# lora.net
KiCad netlist of a schematic drawn in Altium Designer
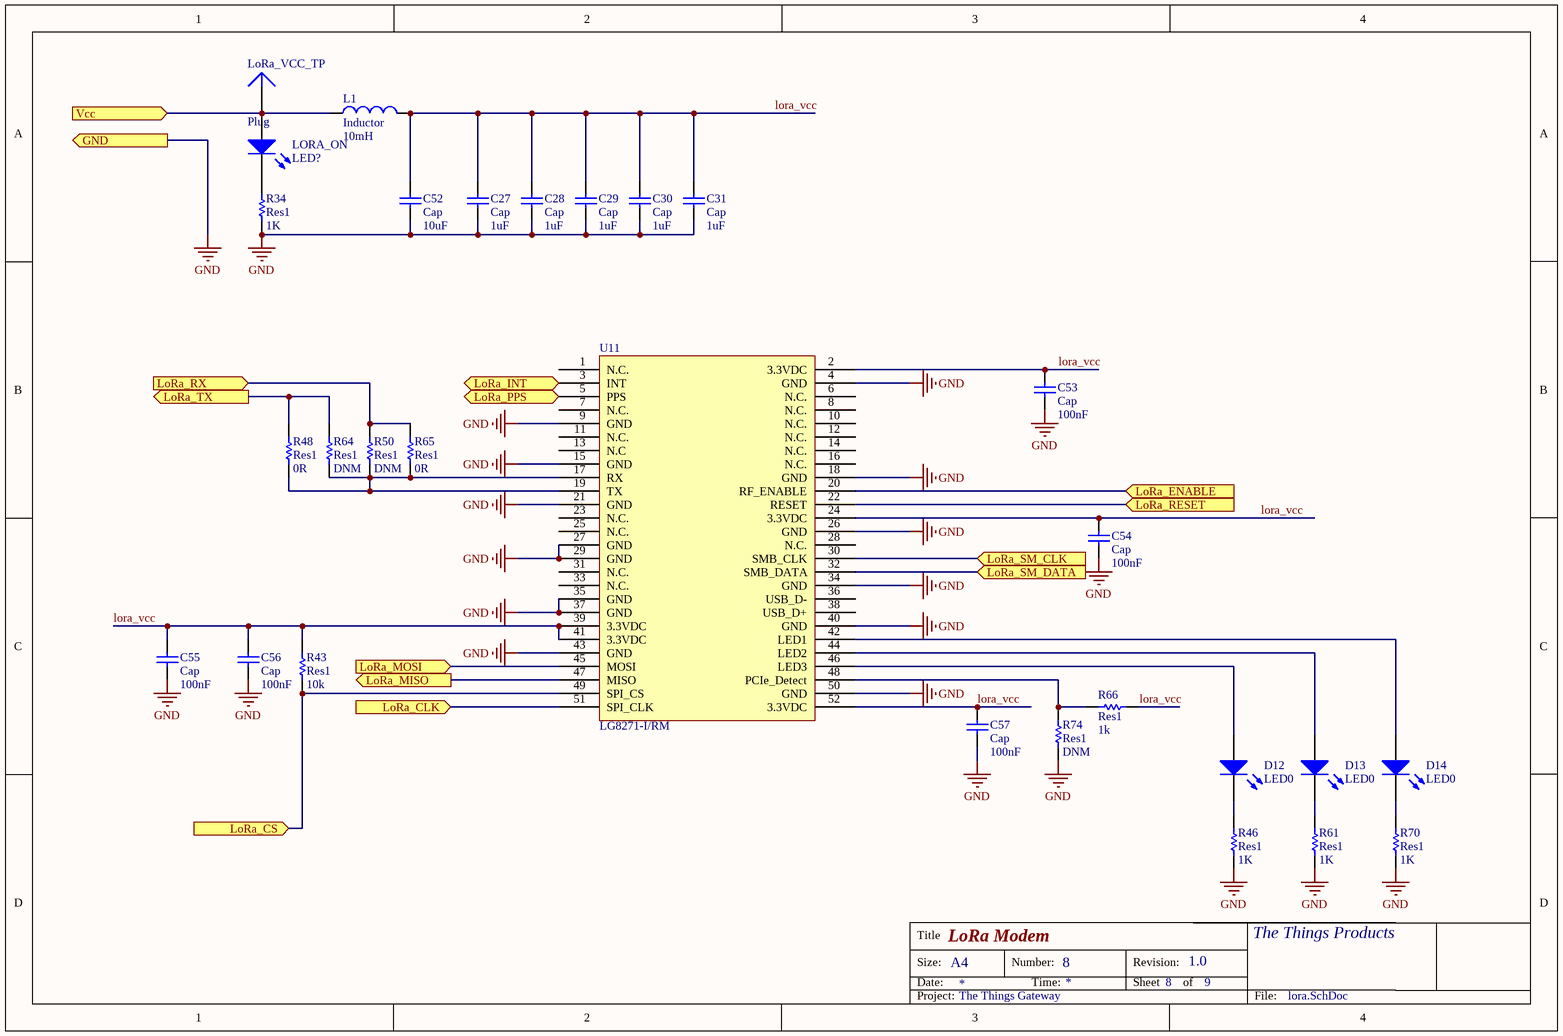
[diagram p0: lora.SchDoc]

(export (version "E")
  (design (tool "Eeschema 10.0.6"))
  (components
    (comp (ref "C27")
      (value "Cap")
      (footprint "C1206")
      (description "Capacitor")
      (fields (field (name "ALTIUM_VALUE") "1uF") (field (name "PUBLISHER") "Altium Limited"))
      (libsource (lib "any") (part "Cap"))
    )
    (comp (ref "C28")
      (value "Cap")
      (footprint "C1206")
      (description "Capacitor")
      (fields (field (name "ALTIUM_VALUE") "1uF") (field (name "PUBLISHER") "Altium Limited"))
      (libsource (lib "any") (part "Cap"))
    )
    (comp (ref "C29")
      (value "Cap")
      (footprint "C1206")
      (description "Capacitor")
      (fields (field (name "ALTIUM_VALUE") "1uF") (field (name "PUBLISHER") "Altium Limited"))
      (libsource (lib "any") (part "Cap"))
    )
    (comp (ref "C30")
      (value "Cap")
      (footprint "C1206")
      (description "Capacitor")
      (fields (field (name "ALTIUM_VALUE") "1uF") (field (name "PUBLISHER") "Altium Limited"))
      (libsource (lib "any") (part "Cap"))
    )
    (comp (ref "C31")
      (value "Cap")
      (footprint "C1206")
      (description "Capacitor")
      (fields (field (name "ALTIUM_VALUE") "1uF") (field (name "PUBLISHER") "Altium Limited"))
      (libsource (lib "any") (part "Cap"))
    )
    (comp (ref "C52")
      (value "Cap")
      (footprint "C1206")
      (description "Capacitor")
      (fields (field (name "ALTIUM_VALUE") "10uF") (field (name "PUBLISHER") "Altium Limited"))
      (libsource (lib "any") (part "Cap"))
    )
    (comp (ref "C53")
      (value "Cap")
      (footprint "C0603")
      (description "Capacitor")
      (fields (field (name "ALTIUM_VALUE") "100nF") (field (name "PUBLISHER") "Altium Limited"))
      (libsource (lib "any") (part "Cap"))
    )
    (comp (ref "C54")
      (value "Cap")
      (footprint "C0603")
      (description "Capacitor")
      (fields (field (name "ALTIUM_VALUE") "100nF") (field (name "PUBLISHER") "Altium Limited"))
      (libsource (lib "any") (part "Cap"))
    )
    (comp (ref "C55")
      (value "Cap")
      (footprint "C0603")
      (description "Capacitor")
      (fields (field (name "ALTIUM_VALUE") "100nF") (field (name "PUBLISHER") "Altium Limited"))
      (libsource (lib "any") (part "Cap"))
    )
    (comp (ref "C56")
      (value "Cap")
      (footprint "C0603")
      (description "Capacitor")
      (fields (field (name "ALTIUM_VALUE") "100nF") (field (name "PUBLISHER") "Altium Limited"))
      (libsource (lib "any") (part "Cap"))
    )
    (comp (ref "C57")
      (value "Cap")
      (footprint "C0603")
      (description "Capacitor")
      (fields (field (name "ALTIUM_VALUE") "100nF") (field (name "PUBLISHER") "Altium Limited"))
      (libsource (lib "any") (part "Cap"))
    )
    (comp (ref "D12")
      (value "LED0")
      (footprint "C0603")
      (description "Typical INFRARED GaAs LED")
      (fields (field (name "PUBLISHER") "Altium Limited"))
      (libsource (lib "any") (part "LED0"))
    )
    (comp (ref "D13")
      (value "LED0")
      (footprint "C0603")
      (description "Typical INFRARED GaAs LED")
      (fields (field (name "PUBLISHER") "Altium Limited"))
      (libsource (lib "any") (part "LED0"))
    )
    (comp (ref "D14")
      (value "LED0")
      (footprint "C0603")
      (description "Typical INFRARED GaAs LED")
      (fields (field (name "PUBLISHER") "Altium Limited"))
      (libsource (lib "any") (part "LED0"))
    )
    (comp (ref "L1")
      (value "Inductor")
      (footprint "2029")
      (fields (field (name "ALTIUM_VALUE") "10mH") (field (name "PUBLISHER") "Altium Limited"))
      (libsource (lib "Miscellaneous Devices") (part "Inductor"))
    )
    (comp (ref "LORA_ON")
      (value "LED?")
      (footprint "C0603")
      (description "Typical INFRARED GaAs LED")
      (fields (field (name "PUBLISHER") "Altium Limited"))
      (libsource (lib "any") (part "LED0"))
    )
    (comp (ref "LoRa_VCC_TP")
      (value "Plug")
      (footprint "PIN1")
      (fields (field (name "PUBLISHER") "Altium Limited"))
      (libsource (lib "Miscellaneous Connectors") (part "Plug"))
    )
    (comp (ref "R34")
      (value "Res1")
      (footprint "R0603")
      (description "Resistor")
      (fields (field (name "ALTIUM_VALUE") "1K") (field (name "PUBLISHER") "Altium Limited"))
      (libsource (lib "any") (part "Res1"))
    )
    (comp (ref "R43")
      (value "Res1")
      (footprint "R0603")
      (description "Resistor")
      (fields (field (name "ALTIUM_VALUE") "10k") (field (name "PUBLISHER") "Altium Limited"))
      (libsource (lib "any") (part "Res1"))
    )
    (comp (ref "R46")
      (value "Res1")
      (footprint "R0603")
      (description "Resistor")
      (fields (field (name "ALTIUM_VALUE") "1K") (field (name "PUBLISHER") "Altium Limited"))
      (libsource (lib "any") (part "Res1"))
    )
    (comp (ref "R48")
      (value "Res1")
      (footprint "R0603")
      (description "Resistor")
      (fields (field (name "ALTIUM_VALUE") "0R") (field (name "PUBLISHER") "Altium Limited"))
      (libsource (lib "any") (part "Res1"))
    )
    (comp (ref "R50")
      (value "Res1")
      (footprint "R0603")
      (description "Resistor")
      (fields (field (name "ALTIUM_VALUE") "DNM") (field (name "PUBLISHER") "Altium Limited"))
      (libsource (lib "any") (part "Res1"))
    )
    (comp (ref "R61")
      (value "Res1")
      (footprint "R0603")
      (description "Resistor")
      (fields (field (name "ALTIUM_VALUE") "1K") (field (name "PUBLISHER") "Altium Limited"))
      (libsource (lib "any") (part "Res1"))
    )
    (comp (ref "R64")
      (value "Res1")
      (footprint "R0603")
      (description "Resistor")
      (fields (field (name "ALTIUM_VALUE") "DNM") (field (name "PUBLISHER") "Altium Limited"))
      (libsource (lib "any") (part "Res1"))
    )
    (comp (ref "R65")
      (value "Res1")
      (footprint "R0603")
      (description "Resistor")
      (fields (field (name "ALTIUM_VALUE") "0R") (field (name "PUBLISHER") "Altium Limited"))
      (libsource (lib "any") (part "Res1"))
    )
    (comp (ref "R66")
      (value "Res1")
      (footprint "R0603")
      (description "Resistor")
      (fields (field (name "ALTIUM_VALUE") "1k") (field (name "PUBLISHER") "Altium Limited"))
      (libsource (lib "any") (part "Res1"))
    )
    (comp (ref "R70")
      (value "Res1")
      (footprint "R0603")
      (description "Resistor")
      (fields (field (name "ALTIUM_VALUE") "1K") (field (name "PUBLISHER") "Altium Limited"))
      (libsource (lib "any") (part "Res1"))
    )
    (comp (ref "R74")
      (value "Res1")
      (footprint "R0603")
      (description "Resistor")
      (fields (field (name "ALTIUM_VALUE") "DNM") (field (name "PUBLISHER") "Altium Limited"))
      (libsource (lib "any") (part "Res1"))
    )
    (comp (ref "U11")
      (value "LG8271-I/RM")
      (footprint "BTB-SM0-8-2H52F")
      (description "Microchip Mini PCI Express LoRa Radio")
      (libsource (lib "ttn_schematic_library") (part "MCP LoRa Gateway"))
    )
  )
  (nets
    (net (code "1") (name "/LoRa_CLK") (class "Default")
      (node (ref "U11") (pin "51") (pinfunction "SPI_CLK_51") (pintype "passive"))
    )
    (net (code "2") (name "/LoRa_CS") (class "Default")
      (node (ref "R43") (pin "1") (pinfunction "1_1") (pintype "passive"))
      (node (ref "U11") (pin "49") (pinfunction "SPI_CS_49") (pintype "passive"))
    )
    (net (code "3") (name "/LoRa_ENABLE") (class "Default")
      (node (ref "U11") (pin "20") (pinfunction "RF_ENABLE_20") (pintype "passive"))
    )
    (net (code "4") (name "/LoRa_INT") (class "Default")
      (node (ref "U11") (pin "3") (pinfunction "INT_3") (pintype "passive"))
    )
    (net (code "5") (name "/LoRa_MISO") (class "Default")
      (node (ref "U11") (pin "47") (pinfunction "MISO_47") (pintype "passive"))
    )
    (net (code "6") (name "/LoRa_MOSI") (class "Default")
      (node (ref "U11") (pin "45") (pinfunction "MOSI_45") (pintype "passive"))
    )
    (net (code "7") (name "/LoRa_PPS") (class "Default")
      (node (ref "U11") (pin "5") (pinfunction "PPS_5") (pintype "passive"))
    )
    (net (code "8") (name "/LoRa_RESET") (class "Default")
      (node (ref "U11") (pin "22") (pinfunction "RESET_22") (pintype "passive"))
    )
    (net (code "9") (name "/LoRa_RX") (class "Default")
      (node (ref "R50") (pin "2") (pinfunction "2_2") (pintype "passive"))
      (node (ref "R65") (pin "1") (pinfunction "1_1") (pintype "passive"))
    )
    (net (code "10") (name "/LoRa_SM_CLK") (class "Default")
      (node (ref "U11") (pin "30") (pinfunction "SMB_CLK_30") (pintype "passive"))
    )
    (net (code "11") (name "/LoRa_SM_DATA") (class "Default")
      (node (ref "U11") (pin "32") (pinfunction "SMB_DATA_32") (pintype "passive"))
    )
    (net (code "12") (name "/LoRa_TX") (class "Default")
      (node (ref "R48") (pin "2") (pinfunction "2_2") (pintype "passive"))
      (node (ref "R64") (pin "2") (pinfunction "2_2") (pintype "passive"))
    )
    (net (code "13") (name "/Vcc") (class "Default")
      (node (ref "L1") (pin "1") (pinfunction "1_1") (pintype "passive"))
      (node (ref "LORA_ON") (pin "1") (pinfunction "A_1") (pintype "passive"))
      (node (ref "LoRa_VCC_TP") (pin "1") (pinfunction "1_1") (pintype "passive"))
    )
    (net (code "14") (name "/lora_vcc") (class "Default")
      (node (ref "C27") (pin "2") (pinfunction "2_2") (pintype "passive"))
      (node (ref "C28") (pin "2") (pinfunction "2_2") (pintype "passive"))
      (node (ref "C29") (pin "2") (pinfunction "2_2") (pintype "passive"))
      (node (ref "C30") (pin "2") (pinfunction "2_2") (pintype "passive"))
      (node (ref "C31") (pin "2") (pinfunction "2_2") (pintype "passive"))
      (node (ref "C52") (pin "2") (pinfunction "2_2") (pintype "passive"))
      (node (ref "C53") (pin "2") (pinfunction "2_2") (pintype "passive"))
      (node (ref "C54") (pin "2") (pinfunction "2_2") (pintype "passive"))
      (node (ref "C55") (pin "2") (pinfunction "2_2") (pintype "passive"))
      (node (ref "C56") (pin "2") (pinfunction "2_2") (pintype "passive"))
      (node (ref "C57") (pin "2") (pinfunction "2_2") (pintype "passive"))
      (node (ref "L1") (pin "2") (pinfunction "2_2") (pintype "passive"))
      (node (ref "R43") (pin "2") (pinfunction "2_2") (pintype "passive"))
      (node (ref "R66") (pin "1") (pinfunction "1_1") (pintype "passive"))
      (node (ref "U11") (pin "2") (pinfunction "3.3VDC_2") (pintype "passive"))
      (node (ref "U11") (pin "24") (pinfunction "3.3VDC_24") (pintype "passive"))
      (node (ref "U11") (pin "39") (pinfunction "3.3VDC_39") (pintype "passive"))
      (node (ref "U11") (pin "41") (pinfunction "3.3VDC_41") (pintype "passive"))
      (node (ref "U11") (pin "52") (pinfunction "3.3VDC_52") (pintype "passive"))
    )
    (net (code "15") (name "GND") (class "Default")
      (node (ref "C27") (pin "1") (pinfunction "1_1") (pintype "passive"))
      (node (ref "C28") (pin "1") (pinfunction "1_1") (pintype "passive"))
      (node (ref "C29") (pin "1") (pinfunction "1_1") (pintype "passive"))
      (node (ref "C30") (pin "1") (pinfunction "1_1") (pintype "passive"))
      (node (ref "C31") (pin "1") (pinfunction "1_1") (pintype "passive"))
      (node (ref "C52") (pin "1") (pinfunction "1_1") (pintype "passive"))
      (node (ref "C53") (pin "1") (pinfunction "1_1") (pintype "passive"))
      (node (ref "C54") (pin "1") (pinfunction "1_1") (pintype "passive"))
      (node (ref "C55") (pin "1") (pinfunction "1_1") (pintype "passive"))
      (node (ref "C56") (pin "1") (pinfunction "1_1") (pintype "passive"))
      (node (ref "C57") (pin "1") (pinfunction "1_1") (pintype "passive"))
      (node (ref "R34") (pin "1") (pinfunction "1_1") (pintype "passive"))
      (node (ref "R46") (pin "1") (pinfunction "1_1") (pintype "passive"))
      (node (ref "R61") (pin "1") (pinfunction "1_1") (pintype "passive"))
      (node (ref "R70") (pin "1") (pinfunction "1_1") (pintype "passive"))
      (node (ref "R74") (pin "1") (pinfunction "1_1") (pintype "passive"))
      (node (ref "U11") (pin "15") (pinfunction "GND_15") (pintype "passive"))
      (node (ref "U11") (pin "18") (pinfunction "GND_18") (pintype "passive"))
      (node (ref "U11") (pin "21") (pinfunction "GND_21") (pintype "passive"))
      (node (ref "U11") (pin "26") (pinfunction "GND_26") (pintype "passive"))
      (node (ref "U11") (pin "27") (pinfunction "GND_27") (pintype "passive"))
      (node (ref "U11") (pin "29") (pinfunction "GND_29") (pintype "passive"))
      (node (ref "U11") (pin "34") (pinfunction "GND_34") (pintype "passive"))
      (node (ref "U11") (pin "35") (pinfunction "GND_35") (pintype "passive"))
      (node (ref "U11") (pin "37") (pinfunction "GND_37") (pintype "passive"))
      (node (ref "U11") (pin "4") (pinfunction "GND_4") (pintype "passive"))
      (node (ref "U11") (pin "40") (pinfunction "GND_40") (pintype "passive"))
      (node (ref "U11") (pin "43") (pinfunction "GND_43") (pintype "passive"))
      (node (ref "U11") (pin "50") (pinfunction "GND_50") (pintype "passive"))
      (node (ref "U11") (pin "9") (pinfunction "GND_9") (pintype "passive"))
    )
    (net (code "16") (name "Net-(D12-A)") (class "Default")
      (node (ref "D12") (pin "1") (pinfunction "A_1") (pintype "passive"))
      (node (ref "U11") (pin "46") (pinfunction "LED3_46") (pintype "passive"))
    )
    (net (code "17") (name "Net-(D12-K)") (class "Default")
      (node (ref "D12") (pin "2") (pinfunction "K_2") (pintype "passive"))
      (node (ref "R46") (pin "2") (pinfunction "2_2") (pintype "passive"))
    )
    (net (code "18") (name "Net-(D13-A)") (class "Default")
      (node (ref "D13") (pin "1") (pinfunction "A_1") (pintype "passive"))
      (node (ref "U11") (pin "44") (pinfunction "LED2_44") (pintype "passive"))
    )
    (net (code "19") (name "Net-(D13-K)") (class "Default")
      (node (ref "D13") (pin "2") (pinfunction "K_2") (pintype "passive"))
      (node (ref "R61") (pin "2") (pinfunction "2_2") (pintype "passive"))
    )
    (net (code "20") (name "Net-(D14-A)") (class "Default")
      (node (ref "D14") (pin "1") (pinfunction "A_1") (pintype "passive"))
      (node (ref "U11") (pin "42") (pinfunction "LED1_42") (pintype "passive"))
    )
    (net (code "21") (name "Net-(D14-K)") (class "Default")
      (node (ref "D14") (pin "2") (pinfunction "K_2") (pintype "passive"))
      (node (ref "R70") (pin "2") (pinfunction "2_2") (pintype "passive"))
    )
    (net (code "22") (name "Net-(LORA_ON-K)") (class "Default")
      (node (ref "LORA_ON") (pin "2") (pinfunction "K_2") (pintype "passive"))
      (node (ref "R34") (pin "2") (pinfunction "2_2") (pintype "passive"))
    )
    (net (code "23") (name "Net-(U11-PCIe_Detect)") (class "Default")
      (node (ref "R66") (pin "2") (pinfunction "2_2") (pintype "passive"))
      (node (ref "R74") (pin "2") (pinfunction "2_2") (pintype "passive"))
      (node (ref "U11") (pin "48") (pinfunction "PCIe_Detect_48") (pintype "passive"))
    )
    (net (code "24") (name "Net-(U11-RX)") (class "Default")
      (node (ref "R48") (pin "1") (pinfunction "1_1") (pintype "passive"))
      (node (ref "R50") (pin "1") (pinfunction "1_1") (pintype "passive"))
      (node (ref "R64") (pin "1") (pinfunction "1_1") (pintype "passive"))
      (node (ref "R65") (pin "2") (pinfunction "2_2") (pintype "passive"))
      (node (ref "U11") (pin "17") (pinfunction "RX_17") (pintype "passive"))
      (node (ref "U11") (pin "19") (pinfunction "TX_19") (pintype "passive"))
    )
    (net (code "25") (name "unconnected-(U11-N.C-Pad13)") (class "Default")
      (node (ref "U11") (pin "13") (pinfunction "N.C_13") (pintype "passive"))
    )
    (net (code "26") (name "unconnected-(U11-N.C.-Pad1)") (class "Default")
      (node (ref "U11") (pin "1") (pinfunction "N.C._1") (pintype "passive"))
    )
    (net (code "27") (name "unconnected-(U11-N.C.-Pad6)") (class "Default")
      (node (ref "U11") (pin "6") (pinfunction "N.C._6") (pintype "passive"))
    )
    (net (code "28") (name "unconnected-(U11-N.C.-Pad7)") (class "Default")
      (node (ref "U11") (pin "7") (pinfunction "N.C._7") (pintype "passive"))
    )
    (net (code "29") (name "unconnected-(U11-N.C.-Pad8)") (class "Default")
      (node (ref "U11") (pin "8") (pinfunction "N.C._8") (pintype "passive"))
    )
    (net (code "30") (name "unconnected-(U11-N.C.-Pad10)") (class "Default")
      (node (ref "U11") (pin "10") (pinfunction "N.C._10") (pintype "passive"))
    )
    (net (code "31") (name "unconnected-(U11-N.C.-Pad11)") (class "Default")
      (node (ref "U11") (pin "11") (pinfunction "N.C._11") (pintype "passive"))
    )
    (net (code "32") (name "unconnected-(U11-N.C.-Pad12)") (class "Default")
      (node (ref "U11") (pin "12") (pinfunction "N.C._12") (pintype "passive"))
    )
    (net (code "33") (name "unconnected-(U11-N.C.-Pad14)") (class "Default")
      (node (ref "U11") (pin "14") (pinfunction "N.C._14") (pintype "passive"))
    )
    (net (code "34") (name "unconnected-(U11-N.C.-Pad16)") (class "Default")
      (node (ref "U11") (pin "16") (pinfunction "N.C._16") (pintype "passive"))
    )
    (net (code "35") (name "unconnected-(U11-N.C.-Pad23)") (class "Default")
      (node (ref "U11") (pin "23") (pinfunction "N.C._23") (pintype "passive"))
    )
    (net (code "36") (name "unconnected-(U11-N.C.-Pad25)") (class "Default")
      (node (ref "U11") (pin "25") (pinfunction "N.C._25") (pintype "passive"))
    )
    (net (code "37") (name "unconnected-(U11-N.C.-Pad28)") (class "Default")
      (node (ref "U11") (pin "28") (pinfunction "N.C._28") (pintype "passive"))
    )
    (net (code "38") (name "unconnected-(U11-N.C.-Pad31)") (class "Default")
      (node (ref "U11") (pin "31") (pinfunction "N.C._31") (pintype "passive"))
    )
    (net (code "39") (name "unconnected-(U11-N.C.-Pad33)") (class "Default")
      (node (ref "U11") (pin "33") (pinfunction "N.C._33") (pintype "passive"))
    )
    (net (code "40") (name "unconnected-(U11-USB_D+-Pad38)") (class "Default")
      (node (ref "U11") (pin "38") (pinfunction "USB_D+_38") (pintype "passive"))
    )
    (net (code "41") (name "unconnected-(U11-USB_D--Pad36)") (class "Default")
      (node (ref "U11") (pin "36") (pinfunction "USB_D-_36") (pintype "passive"))
    )
  )
)
